# microcontroller.net
KiCad netlist of a schematic drawn in Altium Designer
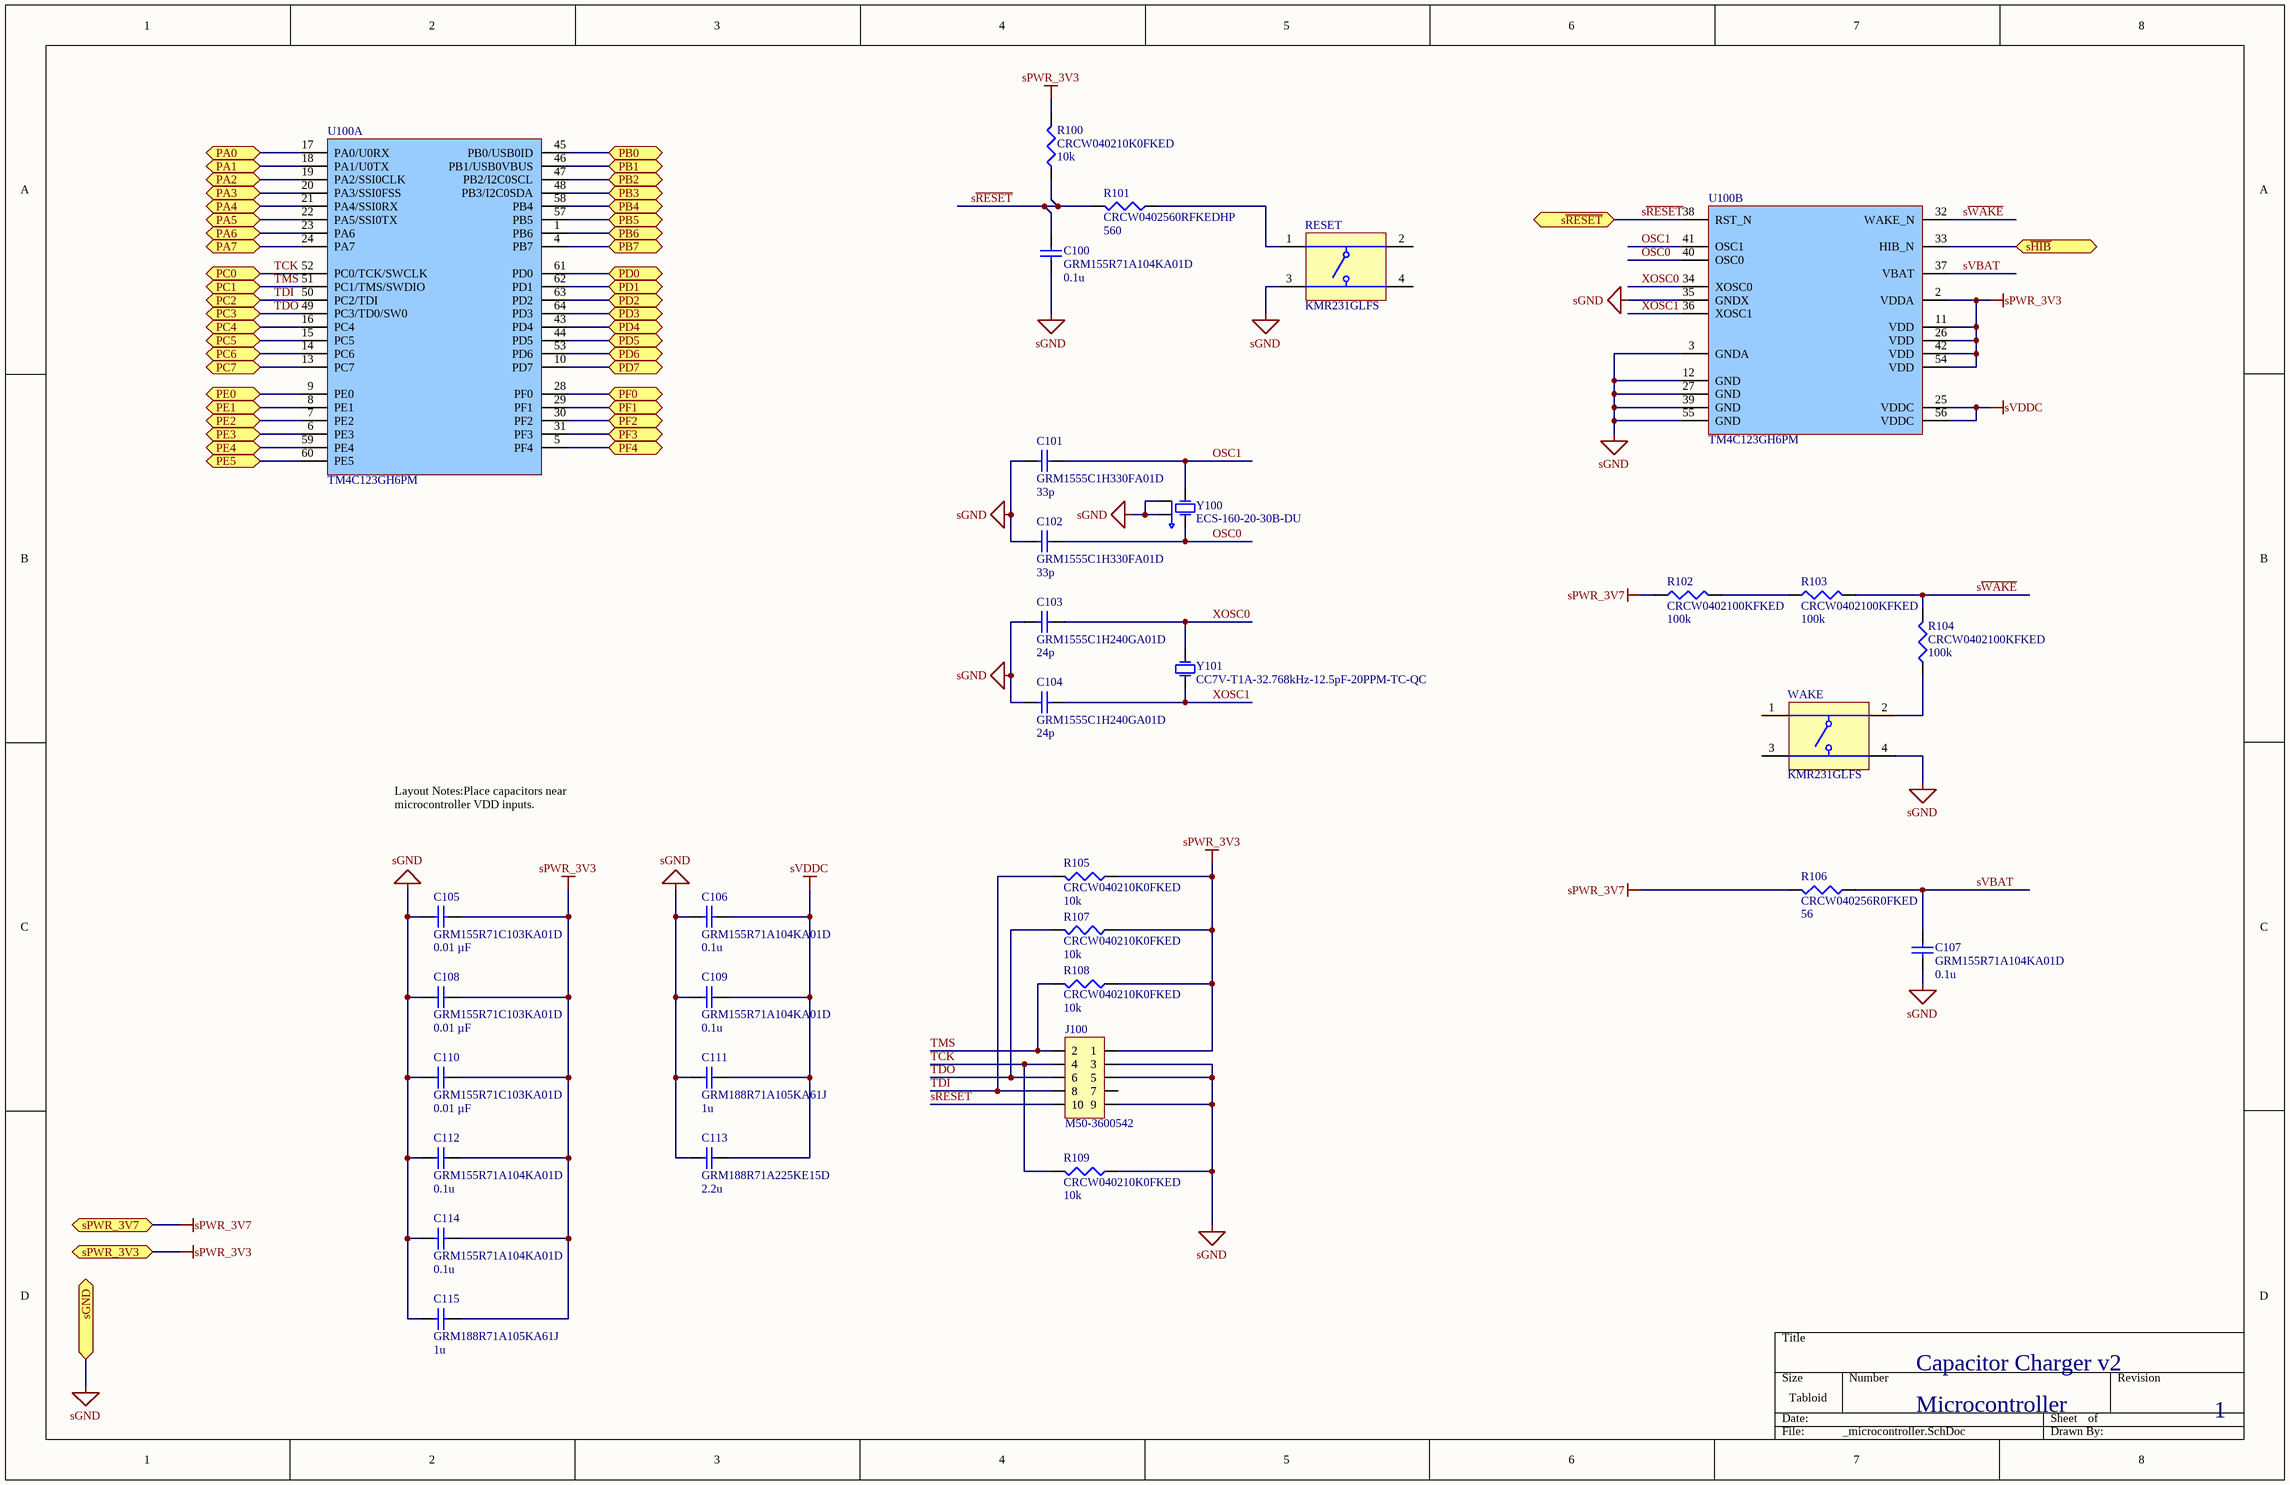
[diagram p0: _microcontroller.SchDoc]

(export (version "E")
  (design (tool "Eeschema 10.0.6"))
  (components
    (comp (ref "C100")
      (value "GRM155R71A104KA01D")
      (footprint "0402")
      (description "-55-125C, 1005, 10V, X7R, ±10%")
      (fields (field (name "ALTIUM_VALUE") "0.1u"))
      (libsource (lib "standard_capacitors") (part "GRM155R71AxxxKdddd"))
    )
    (comp (ref "C101")
      (value "GRM1555C1H330FA01D")
      (footprint "0402")
      (description "Capacitor (Semiconductor SIM Model)")
      (fields (field (name "ALTIUM_VALUE") "33p") (field (name "PUBLISHER") "Altium Limited"))
      (libsource (lib "miscellaneous_devices") (part "Cap Semi"))
    )
    (comp (ref "C102")
      (value "GRM1555C1H330FA01D")
      (footprint "0402")
      (description "Capacitor (Semiconductor SIM Model)")
      (fields (field (name "ALTIUM_VALUE") "33p") (field (name "PUBLISHER") "Altium Limited"))
      (libsource (lib "miscellaneous_devices") (part "Cap Semi"))
    )
    (comp (ref "C103")
      (value "GRM1555C1H240GA01D")
      (footprint "0402")
      (description "Capacitor (Semiconductor SIM Model)")
      (fields (field (name "ALTIUM_VALUE") "24p") (field (name "PUBLISHER") "Altium Limited"))
      (libsource (lib "miscellaneous_devices") (part "Cap Semi"))
    )
    (comp (ref "C104")
      (value "GRM1555C1H240GA01D")
      (footprint "0402")
      (description "Capacitor (Semiconductor SIM Model)")
      (fields (field (name "ALTIUM_VALUE") "24p") (field (name "PUBLISHER") "Altium Limited"))
      (libsource (lib "miscellaneous_devices") (part "Cap Semi"))
    )
    (comp (ref "C105")
      (value "GRM155R71C103KA01D")
      (footprint "0402")
      (description "Cap, 0.01 µF, 16 V, X7R")
      (fields (field (name "ALTIUM_VALUE") "0.01 µF") (field (name "PUBLISHER") "Altium Limited"))
      (libsource (lib "miscellaneous_devices") (part "Cap"))
    )
    (comp (ref "C106")
      (value "GRM155R71A104KA01D")
      (footprint "0402")
      (description "-55-125C, 1005, 10V, X7R, ±10%")
      (fields (field (name "ALTIUM_VALUE") "0.1u"))
      (libsource (lib "standard_capacitors") (part "GRM155R71AxxxKdddd"))
    )
    (comp (ref "C107")
      (value "GRM155R71A104KA01D")
      (footprint "0402")
      (description "-55-125C, 1005, 10V, X7R, ±10%")
      (fields (field (name "ALTIUM_VALUE") "0.1u"))
      (libsource (lib "standard_capacitors") (part "GRM155R71AxxxKdddd"))
    )
    (comp (ref "C108")
      (value "GRM155R71C103KA01D")
      (footprint "0402")
      (description "Cap, 0.01 µF, 16 V, X7R")
      (fields (field (name "ALTIUM_VALUE") "0.01 µF") (field (name "PUBLISHER") "Altium Limited"))
      (libsource (lib "miscellaneous_devices") (part "Cap"))
    )
    (comp (ref "C109")
      (value "GRM155R71A104KA01D")
      (footprint "0402")
      (description "-55-125C, 1005, 10V, X7R, ±10%")
      (fields (field (name "ALTIUM_VALUE") "0.1u"))
      (libsource (lib "standard_capacitors") (part "GRM155R71AxxxKdddd"))
    )
    (comp (ref "C110")
      (value "GRM155R71C103KA01D")
      (footprint "0402")
      (description "Cap, 0.01 µF, 16 V, X7R")
      (fields (field (name "ALTIUM_VALUE") "0.01 µF") (field (name "PUBLISHER") "Altium Limited"))
      (libsource (lib "miscellaneous_devices") (part "Cap"))
    )
    (comp (ref "C111")
      (value "GRM188R71A105KA61J")
      (footprint "0603")
      (description "-55-125C, 1608, 10V, X7R, ±10%")
      (fields (field (name "ALTIUM_VALUE") "1u"))
      (libsource (lib "standard_capacitors") (part "GRM188R71AxxxKdddd"))
    )
    (comp (ref "C112")
      (value "GRM155R71A104KA01D")
      (footprint "0402")
      (description "-55-125C, 1005, 10V, X7R, ±10%")
      (fields (field (name "ALTIUM_VALUE") "0.1u"))
      (libsource (lib "standard_capacitors") (part "GRM155R71AxxxKdddd"))
    )
    (comp (ref "C113")
      (value "GRM188R71A225KE15D")
      (footprint "0603")
      (description "-55-125C, 1608, 10V, X7R, ±10%")
      (fields (field (name "ALTIUM_VALUE") "2.2u"))
      (libsource (lib "standard_capacitors") (part "GRM188R71AxxxKdddd"))
    )
    (comp (ref "C114")
      (value "GRM155R71A104KA01D")
      (footprint "0402")
      (description "-55-125C, 1005, 10V, X7R, ±10%")
      (fields (field (name "ALTIUM_VALUE") "0.1u"))
      (libsource (lib "standard_capacitors") (part "GRM155R71AxxxKdddd"))
    )
    (comp (ref "C115")
      (value "GRM188R71A105KA61J")
      (footprint "0603")
      (description "-55-125C, 1608, 10V, X7R, ±10%")
      (fields (field (name "ALTIUM_VALUE") "1u"))
      (libsource (lib "standard_capacitors") (part "GRM188R71AxxxKdddd"))
    )
    (comp (ref "J100")
      (value "M50-3600542")
      (footprint "M50-3600542")
      (libsource (lib "harwin") (part "M50-3600542"))
    )
    (comp (ref "R100")
      (value "CRCW040210K0FKED")
      (footprint "0402")
      (description "0.125W, -55-155C, 1005, 50V, ±1%")
      (fields (field (name "ALTIUM_VALUE") "10k"))
      (libsource (lib "standard_resistors") (part "CRCW0402xxxxFKED"))
    )
    (comp (ref "R101")
      (value "CRCW0402560RFKEDHP")
      (footprint "0402")
      (description "0.125W, -55-155C, 1005, 50V, ±1%")
      (fields (field (name "ALTIUM_VALUE") "560"))
      (libsource (lib "standard_resistors") (part "CRCW0402xxxxFKED"))
    )
    (comp (ref "R102")
      (value "CRCW0402100KFKED")
      (footprint "0402")
      (description "0.125W, -55-155C, 1005, 50V, ±1%")
      (fields (field (name "ALTIUM_VALUE") "100k"))
      (libsource (lib "standard_resistors") (part "CRCW0402xxxxFKED"))
    )
    (comp (ref "R103")
      (value "CRCW0402100KFKED")
      (footprint "0402")
      (description "0.125W, -55-155C, 1005, 50V, ±1%")
      (fields (field (name "ALTIUM_VALUE") "100k"))
      (libsource (lib "standard_resistors") (part "CRCW0402xxxxFKED"))
    )
    (comp (ref "R104")
      (value "CRCW0402100KFKED")
      (footprint "0402")
      (description "0.125W, -55-155C, 1005, 50V, ±1%")
      (fields (field (name "ALTIUM_VALUE") "100k"))
      (libsource (lib "standard_resistors") (part "CRCW0402xxxxFKED"))
    )
    (comp (ref "R105")
      (value "CRCW040210K0FKED")
      (footprint "0402")
      (description "0.125W, -55-155C, 1005, 50V, ±1%")
      (fields (field (name "ALTIUM_VALUE") "10k"))
      (libsource (lib "standard_resistors") (part "CRCW0402xxxxFKED"))
    )
    (comp (ref "R106")
      (value "CRCW040256R0FKED")
      (footprint "0402")
      (description "0.125W, -55-155C, 1005, 50V, ±1%")
      (fields (field (name "ALTIUM_VALUE") "56"))
      (libsource (lib "standard_resistors") (part "CRCW0402xxxxFKED"))
    )
    (comp (ref "R107")
      (value "CRCW040210K0FKED")
      (footprint "0402")
      (description "0.125W, -55-155C, 1005, 50V, ±1%")
      (fields (field (name "ALTIUM_VALUE") "10k"))
      (libsource (lib "standard_resistors") (part "CRCW0402xxxxFKED"))
    )
    (comp (ref "R108")
      (value "CRCW040210K0FKED")
      (footprint "0402")
      (description "0.125W, -55-155C, 1005, 50V, ±1%")
      (fields (field (name "ALTIUM_VALUE") "10k"))
      (libsource (lib "standard_resistors") (part "CRCW0402xxxxFKED"))
    )
    (comp (ref "R109")
      (value "CRCW040210K0FKED")
      (footprint "0402")
      (description "0.125W, -55-155C, 1005, 50V, ±1%")
      (fields (field (name "ALTIUM_VALUE") "10k"))
      (libsource (lib "standard_resistors") (part "CRCW0402xxxxFKED"))
    )
    (comp (ref "RESET")
      (value "KMR231GLFS")
      (footprint "CKCP-KMR231GLFS")
      (description "Switch Tactile, SPST, 50 mA, 32 V, -40 to 85 degC, 4-Pin SMD, RoHS, Tape and Reel")
      (fields (field (name "MANUFACTURER") "C&K Components"))
      (libsource (lib "Altium Content Vault") (part "CMP-2000-06516-1"))
    )
    (comp (ref "U100")
      (value "TM4C123GH6PM")
      (footprint "QFP50P1200X1200X160-64N")
      (description "Tiva TM4C123GH6PM Microcontroller")
      (libsource (lib "texas_instruments") (part "TM4C123GH6PM"))
    )
    (comp (ref "WAKE")
      (value "KMR231GLFS")
      (footprint "CKCP-KMR231GLFS")
      (description "Switch Tactile, SPST, 50 mA, 32 V, -40 to 85 degC, 4-Pin SMD, RoHS, Tape and Reel")
      (fields (field (name "MANUFACTURER") "C&K Components"))
      (libsource (lib "Altium Content Vault") (part "CMP-2000-06516-1"))
    )
    (comp (ref "Y100")
      (value "ECS-160-20-30B-DU")
      (footprint "ECX-53B")
      (description "Crystal, 16.000MHz, 20pF, 100ppm, -55 to 125 C, 60 Ω")
      (libsource (lib "ecs") (part "ECS-160-20-30B-DU"))
    )
    (comp (ref "Y101")
      (value "CC7V-T1A-32.768kHz-12.5pF-20PPM-TC-QC")
      (footprint "CC7V-T1A")
      (description "Crystals 32.768 kHz 12.5 pF +/-20 PPM -55/+125C")
      (libsource (lib "micro_crystal") (part "CC7V-T1A"))
    )
  )
  (nets
    (net (code "1") (name "/OSC0") (class "Default")
      (node (ref "C102") (pin "2") (pinfunction "2_2") (pintype "passive"))
      (node (ref "U100") (pin "40") (pinfunction "OSC0_40") (pintype "passive"))
      (node (ref "Y100") (pin "3") (pinfunction "3_3") (pintype "passive"))
    )
    (net (code "2") (name "/OSC1") (class "Default")
      (node (ref "C101") (pin "2") (pinfunction "2_2") (pintype "passive"))
      (node (ref "U100") (pin "41") (pinfunction "OSC1_41") (pintype "passive"))
      (node (ref "Y100") (pin "1") (pinfunction "1_1") (pintype "passive"))
    )
    (net (code "3") (name "/PA0") (class "Default")
      (node (ref "U100") (pin "17") (pinfunction "PA0/U0RX_17") (pintype "passive"))
    )
    (net (code "4") (name "/PA1") (class "Default")
      (node (ref "U100") (pin "18") (pinfunction "PA1/U0TX_18") (pintype "passive"))
    )
    (net (code "5") (name "/PA2") (class "Default")
      (node (ref "U100") (pin "19") (pinfunction "PA2/SSI0CLK_19") (pintype "passive"))
    )
    (net (code "6") (name "/PA3") (class "Default")
      (node (ref "U100") (pin "20") (pinfunction "PA3/SSI0FSS_20") (pintype "passive"))
    )
    (net (code "7") (name "/PA4") (class "Default")
      (node (ref "U100") (pin "21") (pinfunction "PA4/SSI0RX_21") (pintype "passive"))
    )
    (net (code "8") (name "/PA5") (class "Default")
      (node (ref "U100") (pin "22") (pinfunction "PA5/SSI0TX_22") (pintype "passive"))
    )
    (net (code "9") (name "/PA6") (class "Default")
      (node (ref "U100") (pin "23") (pinfunction "PA6_23") (pintype "passive"))
    )
    (net (code "10") (name "/PA7") (class "Default")
      (node (ref "U100") (pin "24") (pinfunction "PA7_24") (pintype "passive"))
    )
    (net (code "11") (name "/PB0") (class "Default")
      (node (ref "U100") (pin "45") (pinfunction "PB0/USB0ID_45") (pintype "passive"))
    )
    (net (code "12") (name "/PB1") (class "Default")
      (node (ref "U100") (pin "46") (pinfunction "PB1/USB0VBUS_46") (pintype "passive"))
    )
    (net (code "13") (name "/PB2") (class "Default")
      (node (ref "U100") (pin "47") (pinfunction "PB2/I2C0SCL_47") (pintype "passive"))
    )
    (net (code "14") (name "/PB3") (class "Default")
      (node (ref "U100") (pin "48") (pinfunction "PB3/I2C0SDA_48") (pintype "passive"))
    )
    (net (code "15") (name "/PB4") (class "Default")
      (node (ref "U100") (pin "58") (pinfunction "PB4_58") (pintype "passive"))
    )
    (net (code "16") (name "/PB5") (class "Default")
      (node (ref "U100") (pin "57") (pinfunction "PB5_57") (pintype "passive"))
    )
    (net (code "17") (name "/PB6") (class "Default")
      (node (ref "U100") (pin "1") (pinfunction "PB6_1") (pintype "passive"))
    )
    (net (code "18") (name "/PB7") (class "Default")
      (node (ref "U100") (pin "4") (pinfunction "PB7_4") (pintype "passive"))
    )
    (net (code "19") (name "/PC4") (class "Default")
      (node (ref "U100") (pin "16") (pinfunction "PC4_16") (pintype "passive"))
    )
    (net (code "20") (name "/PC5") (class "Default")
      (node (ref "U100") (pin "15") (pinfunction "PC5_15") (pintype "passive"))
    )
    (net (code "21") (name "/PC6") (class "Default")
      (node (ref "U100") (pin "14") (pinfunction "PC6_14") (pintype "passive"))
    )
    (net (code "22") (name "/PC7") (class "Default")
      (node (ref "U100") (pin "13") (pinfunction "PC7_13") (pintype "passive"))
    )
    (net (code "23") (name "/PD0") (class "Default")
      (node (ref "U100") (pin "61") (pinfunction "PD0_61") (pintype "passive"))
    )
    (net (code "24") (name "/PD1") (class "Default")
      (node (ref "U100") (pin "62") (pinfunction "PD1_62") (pintype "passive"))
    )
    (net (code "25") (name "/PD2") (class "Default")
      (node (ref "U100") (pin "63") (pinfunction "PD2_63") (pintype "passive"))
    )
    (net (code "26") (name "/PD3") (class "Default")
      (node (ref "U100") (pin "64") (pinfunction "PD3_64") (pintype "passive"))
    )
    (net (code "27") (name "/PD4") (class "Default")
      (node (ref "U100") (pin "43") (pinfunction "PD4_43") (pintype "passive"))
    )
    (net (code "28") (name "/PD5") (class "Default")
      (node (ref "U100") (pin "44") (pinfunction "PD5_44") (pintype "passive"))
    )
    (net (code "29") (name "/PD6") (class "Default")
      (node (ref "U100") (pin "53") (pinfunction "PD6_53") (pintype "passive"))
    )
    (net (code "30") (name "/PD7") (class "Default")
      (node (ref "U100") (pin "10") (pinfunction "PD7_10") (pintype "passive"))
    )
    (net (code "31") (name "/PE0") (class "Default")
      (node (ref "U100") (pin "9") (pinfunction "PE0_9") (pintype "passive"))
    )
    (net (code "32") (name "/PE1") (class "Default")
      (node (ref "U100") (pin "8") (pinfunction "PE1_8") (pintype "passive"))
    )
    (net (code "33") (name "/PE2") (class "Default")
      (node (ref "U100") (pin "7") (pinfunction "PE2_7") (pintype "passive"))
    )
    (net (code "34") (name "/PE3") (class "Default")
      (node (ref "U100") (pin "6") (pinfunction "PE3_6") (pintype "passive"))
    )
    (net (code "35") (name "/PE4") (class "Default")
      (node (ref "U100") (pin "59") (pinfunction "PE4_59") (pintype "passive"))
    )
    (net (code "36") (name "/PE5") (class "Default")
      (node (ref "U100") (pin "60") (pinfunction "PE5_60") (pintype "passive"))
    )
    (net (code "37") (name "/PF0") (class "Default")
      (node (ref "U100") (pin "28") (pinfunction "PF0_28") (pintype "passive"))
    )
    (net (code "38") (name "/PF1") (class "Default")
      (node (ref "U100") (pin "29") (pinfunction "PF1_29") (pintype "passive"))
    )
    (net (code "39") (name "/PF2") (class "Default")
      (node (ref "U100") (pin "30") (pinfunction "PF2_30") (pintype "passive"))
    )
    (net (code "40") (name "/PF3") (class "Default")
      (node (ref "U100") (pin "31") (pinfunction "PF3_31") (pintype "passive"))
    )
    (net (code "41") (name "/PF4") (class "Default")
      (node (ref "U100") (pin "5") (pinfunction "PF4_5") (pintype "passive"))
    )
    (net (code "42") (name "/TCK") (class "Default")
      (node (ref "J100") (pin "4") (pinfunction "4_4") (pintype "passive"))
      (node (ref "R109") (pin "2") (pinfunction "2_2") (pintype "passive"))
      (node (ref "U100") (pin "52") (pinfunction "PC0/TCK/SWCLK_52") (pintype "passive"))
    )
    (net (code "43") (name "/TDI") (class "Default")
      (node (ref "J100") (pin "8") (pinfunction "8_8") (pintype "passive"))
      (node (ref "R105") (pin "2") (pinfunction "2_2") (pintype "passive"))
      (node (ref "U100") (pin "50") (pinfunction "PC2/TDI_50") (pintype "passive"))
    )
    (net (code "44") (name "/TDO") (class "Default")
      (node (ref "J100") (pin "6") (pinfunction "6_6") (pintype "passive"))
      (node (ref "R107") (pin "2") (pinfunction "2_2") (pintype "passive"))
      (node (ref "U100") (pin "49") (pinfunction "PC3/TD0/SW0_49") (pintype "passive"))
    )
    (net (code "45") (name "/TMS") (class "Default")
      (node (ref "J100") (pin "2") (pinfunction "2_2") (pintype "passive"))
      (node (ref "R108") (pin "2") (pinfunction "2_2") (pintype "passive"))
      (node (ref "U100") (pin "51") (pinfunction "PC1/TMS/SWDIO_51") (pintype "passive"))
    )
    (net (code "46") (name "/XOSC0") (class "Default")
      (node (ref "C103") (pin "2") (pinfunction "2_2") (pintype "passive"))
      (node (ref "U100") (pin "34") (pinfunction "XOSC0_34") (pintype "passive"))
      (node (ref "Y101") (pin "1") (pinfunction "1_1") (pintype "passive"))
    )
    (net (code "47") (name "/XOSC1") (class "Default")
      (node (ref "C104") (pin "2") (pinfunction "2_2") (pintype "passive"))
      (node (ref "U100") (pin "36") (pinfunction "XOSC1_36") (pintype "passive"))
      (node (ref "Y101") (pin "2") (pinfunction "2_2") (pintype "passive"))
    )
    (net (code "48") (name "/sVBAT") (class "Default")
      (node (ref "C107") (pin "1") (pinfunction "1_1") (pintype "passive"))
      (node (ref "R106") (pin "1") (pinfunction "1_1") (pintype "passive"))
      (node (ref "U100") (pin "37") (pinfunction "VBAT_37") (pintype "passive"))
    )
    (net (code "49") (name "/s~{HIB}") (class "Default")
      (node (ref "U100") (pin "33") (pinfunction "HIB_N_33") (pintype "passive"))
    )
    (net (code "50") (name "/s~{RESET}") (class "Default")
      (node (ref "C100") (pin "1") (pinfunction "1_1") (pintype "passive"))
      (node (ref "J100") (pin "10") (pinfunction "10_10") (pintype "passive"))
      (node (ref "R100") (pin "1") (pinfunction "1_1") (pintype "passive"))
      (node (ref "R101") (pin "2") (pinfunction "2_2") (pintype "passive"))
      (node (ref "U100") (pin "38") (pinfunction "RST_N_38") (pintype "passive"))
    )
    (net (code "51") (name "/s~{WAKE}") (class "Default")
      (node (ref "R103") (pin "2") (pinfunction "2_2") (pintype "passive"))
      (node (ref "R104") (pin "2") (pinfunction "2_2") (pintype "passive"))
      (node (ref "U100") (pin "32") (pinfunction "WAKE_N_32") (pintype "passive"))
    )
    (net (code "52") (name "Net-(R101-Pad1)") (class "Default")
      (node (ref "R101") (pin "1") (pinfunction "1_1") (pintype "passive"))
      (node (ref "RESET") (pin "1") (pinfunction "1_1") (pintype "passive"))
    )
    (net (code "53") (name "Net-(R102-Pad2)") (class "Default")
      (node (ref "R102") (pin "2") (pinfunction "2_2") (pintype "passive"))
      (node (ref "R103") (pin "1") (pinfunction "1_1") (pintype "passive"))
    )
    (net (code "54") (name "Net-(R104-Pad1)") (class "Default")
      (node (ref "R104") (pin "1") (pinfunction "1_1") (pintype "passive"))
      (node (ref "WAKE") (pin "2") (pinfunction "2_2") (pintype "passive"))
    )
    (net (code "55") (name "sGND") (class "Default")
      (node (ref "C100") (pin "2") (pinfunction "2_2") (pintype "passive"))
      (node (ref "C101") (pin "1") (pinfunction "1_1") (pintype "passive"))
      (node (ref "C102") (pin "1") (pinfunction "1_1") (pintype "passive"))
      (node (ref "C103") (pin "1") (pinfunction "1_1") (pintype "passive"))
      (node (ref "C104") (pin "1") (pinfunction "1_1") (pintype "passive"))
      (node (ref "C105") (pin "2") (pinfunction "2_2") (pintype "passive"))
      (node (ref "C106") (pin "2") (pinfunction "2_2") (pintype "passive"))
      (node (ref "C107") (pin "2") (pinfunction "2_2") (pintype "passive"))
      (node (ref "C108") (pin "2") (pinfunction "2_2") (pintype "passive"))
      (node (ref "C109") (pin "2") (pinfunction "2_2") (pintype "passive"))
      (node (ref "C110") (pin "2") (pinfunction "2_2") (pintype "passive"))
      (node (ref "C111") (pin "2") (pinfunction "2_2") (pintype "passive"))
      (node (ref "C112") (pin "2") (pinfunction "2_2") (pintype "passive"))
      (node (ref "C113") (pin "2") (pinfunction "2_2") (pintype "passive"))
      (node (ref "C114") (pin "2") (pinfunction "2_2") (pintype "passive"))
      (node (ref "C115") (pin "2") (pinfunction "2_2") (pintype "passive"))
      (node (ref "J100") (pin "3") (pinfunction "3_3") (pintype "passive"))
      (node (ref "J100") (pin "5") (pinfunction "5_5") (pintype "passive"))
      (node (ref "J100") (pin "9") (pinfunction "9_9") (pintype "passive"))
      (node (ref "R109") (pin "1") (pinfunction "1_1") (pintype "passive"))
      (node (ref "RESET") (pin "3") (pinfunction "3_3") (pintype "passive"))
      (node (ref "U100") (pin "12") (pinfunction "GND_12") (pintype "passive"))
      (node (ref "U100") (pin "27") (pinfunction "GND_27") (pintype "passive"))
      (node (ref "U100") (pin "3") (pinfunction "GNDA_3") (pintype "passive"))
      (node (ref "U100") (pin "35") (pinfunction "GNDX_35") (pintype "passive"))
      (node (ref "U100") (pin "39") (pinfunction "GND_39") (pintype "passive"))
      (node (ref "U100") (pin "55") (pinfunction "GND_55") (pintype "passive"))
      (node (ref "WAKE") (pin "4") (pinfunction "4_4") (pintype "passive"))
      (node (ref "Y100") (pin "2") (pinfunction "2_2") (pintype "passive"))
      (node (ref "Y100") (pin "4") (pinfunction "4_4") (pintype "passive"))
    )
    (net (code "56") (name "sPWR_3V3") (class "Default")
      (node (ref "C105") (pin "1") (pinfunction "1_1") (pintype "passive"))
      (node (ref "C108") (pin "1") (pinfunction "1_1") (pintype "passive"))
      (node (ref "C110") (pin "1") (pinfunction "1_1") (pintype "passive"))
      (node (ref "C112") (pin "1") (pinfunction "1_1") (pintype "passive"))
      (node (ref "C114") (pin "1") (pinfunction "1_1") (pintype "passive"))
      (node (ref "C115") (pin "1") (pinfunction "1_1") (pintype "passive"))
      (node (ref "J100") (pin "1") (pinfunction "1_1") (pintype "passive"))
      (node (ref "R100") (pin "2") (pinfunction "2_2") (pintype "passive"))
      (node (ref "R105") (pin "1") (pinfunction "1_1") (pintype "passive"))
      (node (ref "R107") (pin "1") (pinfunction "1_1") (pintype "passive"))
      (node (ref "R108") (pin "1") (pinfunction "1_1") (pintype "passive"))
      (node (ref "U100") (pin "11") (pinfunction "VDD_11") (pintype "passive"))
      (node (ref "U100") (pin "2") (pinfunction "VDDA_2") (pintype "passive"))
      (node (ref "U100") (pin "26") (pinfunction "VDD_26") (pintype "passive"))
      (node (ref "U100") (pin "42") (pinfunction "VDD_42") (pintype "passive"))
      (node (ref "U100") (pin "54") (pinfunction "VDD_54") (pintype "passive"))
    )
    (net (code "57") (name "sPWR_3V7") (class "Default")
      (node (ref "R102") (pin "1") (pinfunction "1_1") (pintype "passive"))
      (node (ref "R106") (pin "2") (pinfunction "2_2") (pintype "passive"))
    )
    (net (code "58") (name "sVDDC") (class "Default")
      (node (ref "C106") (pin "1") (pinfunction "1_1") (pintype "passive"))
      (node (ref "C109") (pin "1") (pinfunction "1_1") (pintype "passive"))
      (node (ref "C111") (pin "1") (pinfunction "1_1") (pintype "passive"))
      (node (ref "C113") (pin "1") (pinfunction "1_1") (pintype "passive"))
      (node (ref "U100") (pin "25") (pinfunction "VDDC_25") (pintype "passive"))
      (node (ref "U100") (pin "56") (pinfunction "VDDC_56") (pintype "passive"))
    )
    (net (code "59") (name "unconnected-(J100-Pad7)") (class "Default")
      (node (ref "J100") (pin "7") (pinfunction "7_7") (pintype "passive"))
    )
    (net (code "60") (name "unconnected-(RESET-Pad2)") (class "Default")
      (node (ref "RESET") (pin "2") (pinfunction "2_2") (pintype "passive"))
    )
    (net (code "61") (name "unconnected-(RESET-Pad4)") (class "Default")
      (node (ref "RESET") (pin "4") (pinfunction "4_4") (pintype "passive"))
    )
    (net (code "62") (name "unconnected-(WAKE-Pad1)") (class "Default")
      (node (ref "WAKE") (pin "1") (pinfunction "1_1") (pintype "passive"))
    )
    (net (code "63") (name "unconnected-(WAKE-Pad3)") (class "Default")
      (node (ref "WAKE") (pin "3") (pinfunction "3_3") (pintype "passive"))
    )
  )
)
